# signalgen.net
KiCad netlist of a schematic drawn in EAGLE
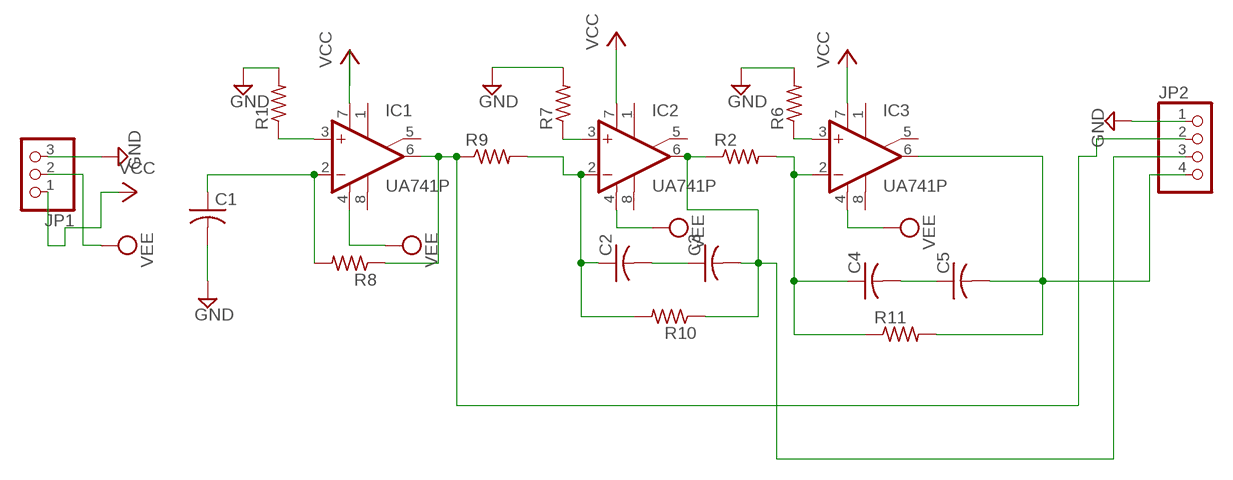
[diagram p0: schematic, sheet 1]

(export (version "E")
  (design (tool "Eeschema 10.0.6"))
  (components
    (comp (ref "C1")
      (value "C-US050-024X044")
      (footprint "eagle-import:C050-024X044")
      (libsource (lib "eagle-import") (part "C-US050-024X044"))
    )
    (comp (ref "C2")
      (value "C-US050-024X044")
      (footprint "eagle-import:C050-024X044")
      (libsource (lib "eagle-import") (part "C-US050-024X044"))
    )
    (comp (ref "C3")
      (value "C-US050-024X044")
      (footprint "eagle-import:C050-024X044")
      (libsource (lib "eagle-import") (part "C-US050-024X044"))
    )
    (comp (ref "C4")
      (value "C-US050-024X044")
      (footprint "eagle-import:C050-024X044")
      (libsource (lib "eagle-import") (part "C-US050-024X044"))
    )
    (comp (ref "C5")
      (value "C-US050-024X044")
      (footprint "eagle-import:C050-024X044")
      (libsource (lib "eagle-import") (part "C-US050-024X044"))
    )
    (comp (ref "IC1")
      (value "UA741P")
      (footprint "eagle-import:DIL08")
      (libsource (lib "eagle-import") (part "741PUA"))
    )
    (comp (ref "IC2")
      (value "UA741P")
      (footprint "eagle-import:DIL08")
      (libsource (lib "eagle-import") (part "741PUA"))
    )
    (comp (ref "IC3")
      (value "UA741P")
      (footprint "eagle-import:DIL08")
      (libsource (lib "eagle-import") (part "741PUA"))
    )
    (comp (ref "JP1")
      (value "PINHD-1X3")
      (footprint "eagle-import:1X03")
      (libsource (lib "eagle-import") (part "PINHD-1X3"))
    )
    (comp (ref "JP2")
      (value "PINHD-1X4")
      (footprint "eagle-import:1X04")
      (libsource (lib "eagle-import") (part "PINHD-1X4"))
    )
    (comp (ref "R1")
      (value "R-US_0207/10")
      (footprint "eagle-import:0207_10")
      (libsource (lib "eagle-import") (part "R-US_0207/10"))
    )
    (comp (ref "R2")
      (value "R-US_0207/10")
      (footprint "eagle-import:0207_10")
      (libsource (lib "eagle-import") (part "R-US_0207/10"))
    )
    (comp (ref "R6")
      (value "R-US_0207/10")
      (footprint "eagle-import:0207_10")
      (libsource (lib "eagle-import") (part "R-US_0207/10"))
    )
    (comp (ref "R7")
      (value "R-US_0207/10")
      (footprint "eagle-import:0207_10")
      (libsource (lib "eagle-import") (part "R-US_0207/10"))
    )
    (comp (ref "R8")
      (value "R-US_0207/10")
      (footprint "eagle-import:0207_10")
      (libsource (lib "eagle-import") (part "R-US_0207/10"))
    )
    (comp (ref "R9")
      (value "R-US_0207/10")
      (footprint "eagle-import:0207_10")
      (libsource (lib "eagle-import") (part "R-US_0207/10"))
    )
    (comp (ref "R10")
      (value "R-US_0207/10")
      (footprint "eagle-import:0207_10")
      (libsource (lib "eagle-import") (part "R-US_0207/10"))
    )
    (comp (ref "R11")
      (value "R-US_0207/10")
      (footprint "eagle-import:0207_10")
      (libsource (lib "eagle-import") (part "R-US_0207/10"))
    )
  )
  (nets
    (net (code "1") (name "GND") (class "Default")
      (node (ref "C1") (pin "2") (pinfunction "2_2") (pintype "passive"))
      (node (ref "JP1") (pin "3") (pinfunction "3_3") (pintype "passive"))
      (node (ref "JP2") (pin "1") (pinfunction "1_1") (pintype "passive"))
      (node (ref "R1") (pin "2") (pinfunction "2_2") (pintype "passive"))
      (node (ref "R6") (pin "2") (pinfunction "2_2") (pintype "passive"))
      (node (ref "R7") (pin "2") (pinfunction "2_2") (pintype "passive"))
    )
    (net (code "2") (name "Net-(C2-Pad2)") (class "Default")
      (node (ref "C2") (pin "2") (pinfunction "2_2") (pintype "passive"))
      (node (ref "C3") (pin "1") (pinfunction "1_1") (pintype "passive"))
    )
    (net (code "3") (name "Net-(C4-Pad2)") (class "Default")
      (node (ref "C4") (pin "2") (pinfunction "2_2") (pintype "passive"))
      (node (ref "C5") (pin "1") (pinfunction "1_1") (pintype "passive"))
    )
    (net (code "4") (name "Net-(IC1-+IN)") (class "Default")
      (node (ref "IC1") (pin "3") (pinfunction "+IN_3") (pintype "input"))
      (node (ref "R1") (pin "1") (pinfunction "1_1") (pintype "passive"))
    )
    (net (code "5") (name "Net-(IC1--IN)") (class "Default")
      (node (ref "C1") (pin "1") (pinfunction "1_1") (pintype "passive"))
      (node (ref "IC1") (pin "2") (pinfunction "-IN_2") (pintype "input"))
      (node (ref "R8") (pin "2") (pinfunction "2_2") (pintype "passive"))
    )
    (net (code "6") (name "Net-(IC1-OUT)") (class "Default")
      (node (ref "IC1") (pin "6") (pinfunction "OUT_6") (pintype "output"))
      (node (ref "JP2") (pin "2") (pinfunction "2_2") (pintype "passive"))
      (node (ref "R8") (pin "1") (pinfunction "1_1") (pintype "passive"))
      (node (ref "R9") (pin "1") (pinfunction "1_1") (pintype "passive"))
    )
    (net (code "7") (name "Net-(IC2-+IN)") (class "Default")
      (node (ref "IC2") (pin "3") (pinfunction "+IN_3") (pintype "input"))
      (node (ref "R7") (pin "1") (pinfunction "1_1") (pintype "passive"))
    )
    (net (code "8") (name "Net-(IC2--IN)") (class "Default")
      (node (ref "C2") (pin "1") (pinfunction "1_1") (pintype "passive"))
      (node (ref "IC2") (pin "2") (pinfunction "-IN_2") (pintype "input"))
      (node (ref "R10") (pin "2") (pinfunction "2_2") (pintype "passive"))
      (node (ref "R9") (pin "2") (pinfunction "2_2") (pintype "passive"))
    )
    (net (code "9") (name "Net-(IC2-OUT)") (class "Default")
      (node (ref "C3") (pin "2") (pinfunction "2_2") (pintype "passive"))
      (node (ref "IC2") (pin "6") (pinfunction "OUT_6") (pintype "output"))
      (node (ref "JP2") (pin "3") (pinfunction "3_3") (pintype "passive"))
      (node (ref "R10") (pin "1") (pinfunction "1_1") (pintype "passive"))
      (node (ref "R2") (pin "1") (pinfunction "1_1") (pintype "passive"))
    )
    (net (code "10") (name "Net-(IC3-+IN)") (class "Default")
      (node (ref "IC3") (pin "3") (pinfunction "+IN_3") (pintype "input"))
      (node (ref "R6") (pin "1") (pinfunction "1_1") (pintype "passive"))
    )
    (net (code "11") (name "Net-(IC3--IN)") (class "Default")
      (node (ref "C4") (pin "1") (pinfunction "1_1") (pintype "passive"))
      (node (ref "IC3") (pin "2") (pinfunction "-IN_2") (pintype "input"))
      (node (ref "R11") (pin "1") (pinfunction "1_1") (pintype "passive"))
      (node (ref "R2") (pin "2") (pinfunction "2_2") (pintype "passive"))
    )
    (net (code "12") (name "Net-(IC3-OUT)") (class "Default")
      (node (ref "C5") (pin "2") (pinfunction "2_2") (pintype "passive"))
      (node (ref "IC3") (pin "6") (pinfunction "OUT_6") (pintype "output"))
      (node (ref "JP2") (pin "4") (pinfunction "4_4") (pintype "passive"))
      (node (ref "R11") (pin "2") (pinfunction "2_2") (pintype "passive"))
    )
    (net (code "13") (name "VCC") (class "Default")
      (node (ref "IC1") (pin "7") (pinfunction "V+_7") (pintype "power_in"))
      (node (ref "IC2") (pin "7") (pinfunction "V+_7") (pintype "power_in"))
      (node (ref "IC3") (pin "7") (pinfunction "V+_7") (pintype "power_in"))
      (node (ref "JP1") (pin "1") (pinfunction "1_1") (pintype "passive"))
    )
    (net (code "14") (name "VEE") (class "Default")
      (node (ref "IC1") (pin "4") (pinfunction "V-_4") (pintype "power_in"))
      (node (ref "IC2") (pin "4") (pinfunction "V-_4") (pintype "power_in"))
      (node (ref "IC3") (pin "4") (pinfunction "V-_4") (pintype "power_in"))
      (node (ref "JP1") (pin "2") (pinfunction "2_2") (pintype "passive"))
    )
    (net (code "15") (name "unconnected-(IC1-ON1-Pad1)") (class "Default")
      (node (ref "IC1") (pin "1") (pinfunction "ON1_1") (pintype "passive"))
    )
    (net (code "16") (name "unconnected-(IC1-ON2-Pad5)") (class "Default")
      (node (ref "IC1") (pin "5") (pinfunction "ON2_5") (pintype "passive"))
    )
    (net (code "17") (name "unconnected-(IC1-OPT-Pad8)") (class "Default")
      (node (ref "IC1") (pin "8") (pinfunction "OPT_8") (pintype "passive"))
    )
    (net (code "18") (name "unconnected-(IC2-ON1-Pad1)") (class "Default")
      (node (ref "IC2") (pin "1") (pinfunction "ON1_1") (pintype "passive"))
    )
    (net (code "19") (name "unconnected-(IC2-ON2-Pad5)") (class "Default")
      (node (ref "IC2") (pin "5") (pinfunction "ON2_5") (pintype "passive"))
    )
    (net (code "20") (name "unconnected-(IC2-OPT-Pad8)") (class "Default")
      (node (ref "IC2") (pin "8") (pinfunction "OPT_8") (pintype "passive"))
    )
    (net (code "21") (name "unconnected-(IC3-ON1-Pad1)") (class "Default")
      (node (ref "IC3") (pin "1") (pinfunction "ON1_1") (pintype "passive"))
    )
    (net (code "22") (name "unconnected-(IC3-ON2-Pad5)") (class "Default")
      (node (ref "IC3") (pin "5") (pinfunction "ON2_5") (pintype "passive"))
    )
    (net (code "23") (name "unconnected-(IC3-OPT-Pad8)") (class "Default")
      (node (ref "IC3") (pin "8") (pinfunction "OPT_8") (pintype "passive"))
    )
  )
)
